# max-night.net
KiCad netlist of a schematic drawn in EAGLE
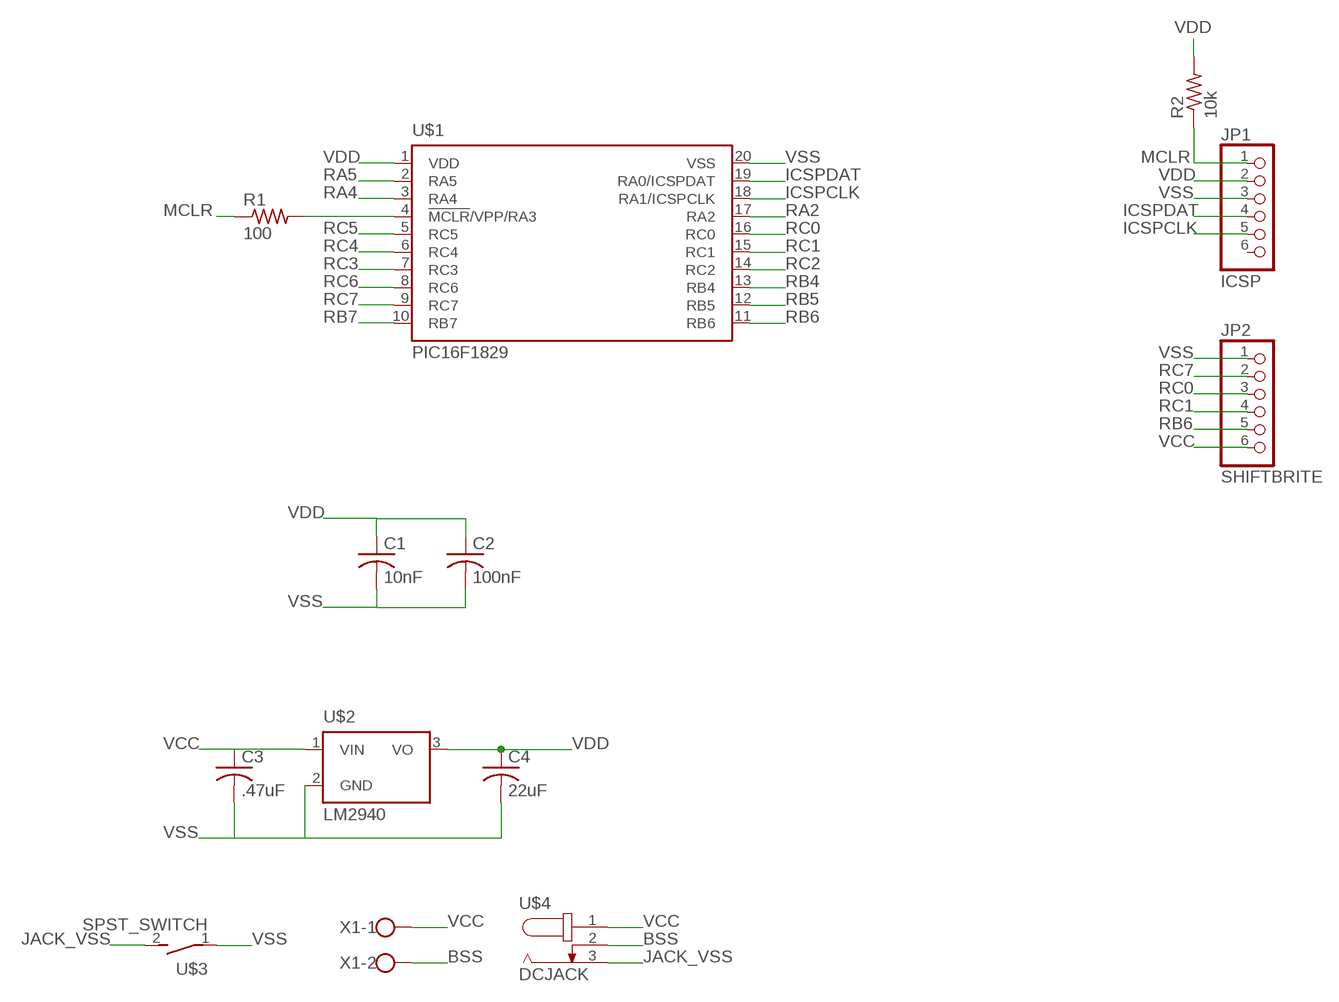
[diagram p0: schematic, sheet 1]

(export (version "E")
  (design (tool "Eeschema 10.0.6"))
  (components
    (comp (ref "C1")
      (value "10nF")
      (footprint "eagle-import:C050-035X075")
      (libsource (lib "eagle-import") (part "C-US050-035X075"))
    )
    (comp (ref "C2")
      (value "100nF")
      (footprint "eagle-import:C050-035X075")
      (libsource (lib "eagle-import") (part "C-US050-035X075"))
    )
    (comp (ref "C3")
      (value ".47uF")
      (footprint "eagle-import:C050-035X075")
      (libsource (lib "eagle-import") (part "C-US050-035X075"))
    )
    (comp (ref "C4")
      (value "22uF")
      (footprint "eagle-import:C050-035X075")
      (libsource (lib "eagle-import") (part "C-US050-035X075"))
    )
    (comp (ref "JP1")
      (value "ICSP")
      (footprint "eagle-import:1X06")
      (libsource (lib "eagle-import") (part "PINHD-1X6"))
    )
    (comp (ref "JP2")
      (value "SHIFTBRITE")
      (footprint "eagle-import:1X06")
      (libsource (lib "eagle-import") (part "PINHD-1X6"))
    )
    (comp (ref "R1")
      (value "100")
      (footprint "eagle-import:0309_12")
      (libsource (lib "eagle-import") (part "R-US_0309/12"))
    )
    (comp (ref "R2")
      (value "10k")
      (footprint "eagle-import:0309_12")
      (libsource (lib "eagle-import") (part "R-US_0309/12"))
    )
    (comp (ref "U$1")
      (value "PIC16F1829")
      (footprint "eagle-import:DIL20")
      (libsource (lib "eagle-import") (part "PIC16F1829"))
    )
    (comp (ref "U$2")
      (value "LM2940")
      (footprint "eagle-import:TO220V")
      (libsource (lib "eagle-import") (part "LM2940"))
    )
    (comp (ref "U$3")
      (value "SPST_SWITCH")
      (footprint "eagle-import:SWITCH_SPST")
      (libsource (lib "eagle-import") (part "SPST_SWITCH"))
    )
    (comp (ref "U$4")
      (value "DCJACK")
      (footprint "eagle-import:DCJACKFP")
      (libsource (lib "eagle-import") (part "DCJACK"))
    )
    (comp (ref "X1")
      (value "W237-102")
      (footprint "eagle-import:W237-102")
      (fields (field (name "MPN") "237-102"))
      (libsource (lib "eagle-import") (part "W237-102"))
    )
  )
  (nets
    (net (code "1") (name "/BSS") (class "Default")
      (node (ref "U$4") (pin "2") (pinfunction "2_2") (pintype "passive"))
      (node (ref "X1") (pin "2") (pinfunction "KL_2") (pintype "passive"))
    )
    (net (code "2") (name "/ICSPCLK") (class "Default")
      (node (ref "JP1") (pin "5") (pinfunction "5_5") (pintype "passive"))
      (node (ref "U$1") (pin "18") (pinfunction "RA1/ICSPCLK_18") (pintype "bidirectional"))
    )
    (net (code "3") (name "/ICSPDAT") (class "Default")
      (node (ref "JP1") (pin "4") (pinfunction "4_4") (pintype "passive"))
      (node (ref "U$1") (pin "19") (pinfunction "RA0/ICSPDAT_19") (pintype "bidirectional"))
    )
    (net (code "4") (name "/JACK_VSS") (class "Default")
      (node (ref "U$3") (pin "2") (pinfunction "S_2") (pintype "passive"))
      (node (ref "U$4") (pin "3") (pinfunction "1_3") (pintype "passive"))
    )
    (net (code "5") (name "/MCLR") (class "Default")
      (node (ref "JP1") (pin "1") (pinfunction "1_1") (pintype "passive"))
      (node (ref "R1") (pin "1") (pinfunction "1_1") (pintype "passive"))
      (node (ref "R2") (pin "1") (pinfunction "1_1") (pintype "passive"))
    )
    (net (code "6") (name "/RA2") (class "Default")
      (node (ref "U$1") (pin "17") (pinfunction "RA2_17") (pintype "bidirectional"))
    )
    (net (code "7") (name "/RA4") (class "Default")
      (node (ref "U$1") (pin "3") (pinfunction "RA4_3") (pintype "bidirectional"))
    )
    (net (code "8") (name "/RA5") (class "Default")
      (node (ref "U$1") (pin "2") (pinfunction "RA5_2") (pintype "bidirectional"))
    )
    (net (code "9") (name "/RB4") (class "Default")
      (node (ref "U$1") (pin "13") (pinfunction "RB4_13") (pintype "bidirectional"))
    )
    (net (code "10") (name "/RB5") (class "Default")
      (node (ref "U$1") (pin "12") (pinfunction "RB5_12") (pintype "power_in"))
    )
    (net (code "11") (name "/RB6") (class "Default")
      (node (ref "JP2") (pin "5") (pinfunction "5_5") (pintype "passive"))
      (node (ref "U$1") (pin "11") (pinfunction "RB6_11") (pintype "power_in"))
    )
    (net (code "12") (name "/RB7") (class "Default")
      (node (ref "U$1") (pin "10") (pinfunction "RB7_10") (pintype "output"))
    )
    (net (code "13") (name "/RC0") (class "Default")
      (node (ref "JP2") (pin "3") (pinfunction "3_3") (pintype "passive"))
      (node (ref "U$1") (pin "16") (pinfunction "RC0_16") (pintype "bidirectional"))
    )
    (net (code "14") (name "/RC1") (class "Default")
      (node (ref "JP2") (pin "4") (pinfunction "4_4") (pintype "passive"))
      (node (ref "U$1") (pin "15") (pinfunction "RC1_15") (pintype "bidirectional"))
    )
    (net (code "15") (name "/RC2") (class "Default")
      (node (ref "U$1") (pin "14") (pinfunction "RC2_14") (pintype "bidirectional"))
    )
    (net (code "16") (name "/RC3") (class "Default")
      (node (ref "U$1") (pin "7") (pinfunction "RC3_7") (pintype "bidirectional"))
    )
    (net (code "17") (name "/RC4") (class "Default")
      (node (ref "U$1") (pin "6") (pinfunction "RC4_6") (pintype "bidirectional"))
    )
    (net (code "18") (name "/RC5") (class "Default")
      (node (ref "U$1") (pin "5") (pinfunction "RC5_5") (pintype "bidirectional"))
    )
    (net (code "19") (name "/RC6") (class "Default")
      (node (ref "U$1") (pin "8") (pinfunction "RC6_8") (pintype "power_in"))
    )
    (net (code "20") (name "/RC7") (class "Default")
      (node (ref "JP2") (pin "2") (pinfunction "2_2") (pintype "passive"))
      (node (ref "U$1") (pin "9") (pinfunction "RC7_9") (pintype "input"))
    )
    (net (code "21") (name "/VCC") (class "Default")
      (node (ref "C3") (pin "1") (pinfunction "1_1") (pintype "passive"))
      (node (ref "JP2") (pin "6") (pinfunction "6_6") (pintype "passive"))
      (node (ref "U$2") (pin "1") (pinfunction "VIN_1") (pintype "input"))
      (node (ref "U$4") (pin "1") (pinfunction "3_1") (pintype "passive"))
      (node (ref "X1") (pin "1") (pinfunction "KL_1") (pintype "passive"))
    )
    (net (code "22") (name "/VDD") (class "Default")
      (node (ref "C1") (pin "1") (pinfunction "1_1") (pintype "passive"))
      (node (ref "C2") (pin "1") (pinfunction "1_1") (pintype "passive"))
      (node (ref "C4") (pin "1") (pinfunction "1_1") (pintype "passive"))
      (node (ref "JP1") (pin "2") (pinfunction "2_2") (pintype "passive"))
      (node (ref "R2") (pin "2") (pinfunction "2_2") (pintype "passive"))
      (node (ref "U$1") (pin "1") (pinfunction "VDD_1") (pintype "input"))
      (node (ref "U$2") (pin "3") (pinfunction "VO_3") (pintype "output"))
    )
    (net (code "23") (name "/VSS") (class "Default")
      (node (ref "C1") (pin "2") (pinfunction "2_2") (pintype "passive"))
      (node (ref "C2") (pin "2") (pinfunction "2_2") (pintype "passive"))
      (node (ref "C3") (pin "2") (pinfunction "2_2") (pintype "passive"))
      (node (ref "C4") (pin "2") (pinfunction "2_2") (pintype "passive"))
      (node (ref "JP1") (pin "3") (pinfunction "3_3") (pintype "passive"))
      (node (ref "JP2") (pin "1") (pinfunction "1_1") (pintype "passive"))
      (node (ref "U$1") (pin "20") (pinfunction "VSS_20") (pintype "bidirectional"))
      (node (ref "U$2") (pin "2") (pinfunction "GND_2") (pintype "passive"))
      (node (ref "U$3") (pin "1") (pinfunction "P_1") (pintype "passive"))
    )
    (net (code "24") (name "Net-(U$1-~{MCLR}{slash}VPP{slash}RA3)") (class "Default")
      (node (ref "R1") (pin "2") (pinfunction "2_2") (pintype "passive"))
      (node (ref "U$1") (pin "4") (pinfunction "~{MCLR}/VPP/RA3_4") (pintype "bidirectional"))
    )
    (net (code "25") (name "unconnected-(JP1-Pad6)") (class "Default")
      (node (ref "JP1") (pin "6") (pinfunction "6_6") (pintype "passive"))
    )
  )
)
